# Connector.net
KiCad netlist of a schematic drawn in Altium Designer
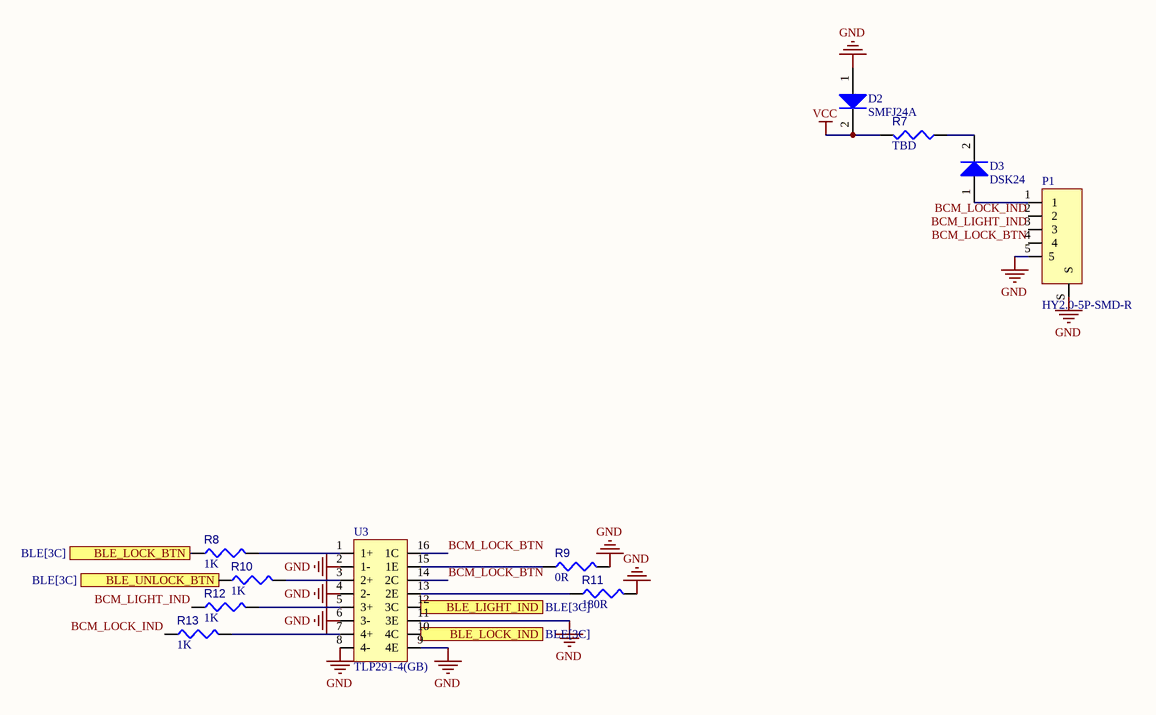
[diagram p0: Connector.SchDoc]

(export (version "E")
  (design (tool "Eeschema 10.0.6"))
  (components
    (comp (ref "D2")
      (value "SMFJ24A")
      (footprint "SOD-123FL")
      (description "TVS Diode")
      (libsource (lib "Database") (part "Diode Symbol"))
    )
    (comp (ref "D3")
      (value "DSK24")
      (footprint "SOD-123FL")
      (description "40V 2A Schottky barrier diode")
      (libsource (lib "Database") (part "Diode Symbol"))
    )
    (comp (ref "P1")
      (value "HY2.0-5P-SMD-R")
      (footprint "HY2.0-5P-SMD-R")
      (description "HY2.0 5P SMD Right angle")
      (libsource (lib "Database") (part "HY2.0-5P-SMD-R"))
    )
    (comp (ref "R7")
      (value "TBD")
      (footprint "RESC2013X70X40LL20T20")
      (description "0805 Universal Chip Resistor")
      (fields (field (name "Comment") "0805 Chip Resistor"))
      (libsource (lib "Database") (part "Chip Resistor"))
    )
    (comp (ref "R8")
      (value "1K")
      (footprint "RESC1608X55X25LL10T15")
      (description "0603 Chip Resistor")
      (fields (field (name "Comment") "1K 0603"))
      (libsource (lib "Database") (part "Chip Resistor"))
    )
    (comp (ref "R9")
      (value "0R")
      (footprint "RESC2013X70X40LL20T20")
      (description "0805 Chip Resistor")
      (fields (field (name "Comment") "0R 0805"))
      (libsource (lib "Database") (part "Chip Resistor"))
    )
    (comp (ref "R10")
      (value "1K")
      (footprint "RESC1608X55X25LL10T15")
      (description "0603 Chip Resistor")
      (fields (field (name "Comment") "1K 0603"))
      (libsource (lib "Database") (part "Chip Resistor"))
    )
    (comp (ref "R11")
      (value "180R")
      (footprint "RESC2013X70X40LL20T20")
      (description "0805 Chip Resistor")
      (fields (field (name "Comment") "180R 0805"))
      (libsource (lib "Database") (part "Chip Resistor"))
    )
    (comp (ref "R12")
      (value "1K")
      (footprint "RESC1608X55X25LL10T15")
      (description "0603 Chip Resistor")
      (fields (field (name "Comment") "1K 0603"))
      (libsource (lib "Database") (part "Chip Resistor"))
    )
    (comp (ref "R13")
      (value "1K")
      (footprint "RESC1608X55X25LL10T15")
      (description "0603 Chip Resistor")
      (fields (field (name "Comment") "1K 0603"))
      (libsource (lib "Database") (part "Chip Resistor"))
    )
    (comp (ref "U3")
      (value "TLP291-4(GB)")
      (footprint "SOP127P700X210-16L")
      (description "Photocouplers GaAs Infrared LED & Photo Transistor CTR 100")
      (libsource (lib "Database") (part "TLP291-4"))
    )
  )
  (nets
    (net (code "1") (name "/BCM_LIGHT_IND") (class "Default")
      (node (ref "P1") (pin "3") (pinfunction "3_3") (pintype "passive"))
      (node (ref "R12") (pin "1") (pinfunction "1_1") (pintype "passive"))
    )
    (net (code "2") (name "/BCM_LOCK_BTN") (class "Default")
      (node (ref "P1") (pin "4") (pinfunction "4_4") (pintype "passive"))
      (node (ref "U3") (pin "14") (pinfunction "2C_14") (pintype "passive"))
      (node (ref "U3") (pin "16") (pinfunction "1C_16") (pintype "passive"))
    )
    (net (code "3") (name "/BCM_LOCK_IND") (class "Default")
      (node (ref "P1") (pin "2") (pinfunction "2_2") (pintype "passive"))
      (node (ref "R13") (pin "1") (pinfunction "1_1") (pintype "passive"))
    )
    (net (code "4") (name "/BLE_LIGHT_IND") (class "Default")
      (node (ref "U3") (pin "12") (pinfunction "3C_12") (pintype "passive"))
    )
    (net (code "5") (name "/BLE_LOCK_BTN") (class "Default")
      (node (ref "R8") (pin "1") (pinfunction "1_1") (pintype "passive"))
    )
    (net (code "6") (name "/BLE_LOCK_IND") (class "Default")
      (node (ref "U3") (pin "10") (pinfunction "4C_10") (pintype "passive"))
    )
    (net (code "7") (name "/BLE_UNLOCK_BTN") (class "Default")
      (node (ref "R10") (pin "1") (pinfunction "1_1") (pintype "passive"))
    )
    (net (code "8") (name "GND") (class "Default")
      (node (ref "D2") (pin "1") (pinfunction "A_1") (pintype "passive"))
      (node (ref "P1") (pin "5") (pinfunction "5_5") (pintype "passive"))
      (node (ref "P1") (pin "S") (pinfunction "S_S") (pintype "passive"))
      (node (ref "R11") (pin "2") (pinfunction "2_2") (pintype "passive"))
      (node (ref "R9") (pin "2") (pinfunction "2_2") (pintype "passive"))
      (node (ref "U3") (pin "11") (pinfunction "3E_11") (pintype "passive"))
      (node (ref "U3") (pin "2") (pinfunction "1-_2") (pintype "passive"))
      (node (ref "U3") (pin "4") (pinfunction "2-_4") (pintype "passive"))
      (node (ref "U3") (pin "6") (pinfunction "3-_6") (pintype "passive"))
      (node (ref "U3") (pin "8") (pinfunction "4-_8") (pintype "passive"))
      (node (ref "U3") (pin "9") (pinfunction "4E_9") (pintype "passive"))
    )
    (net (code "9") (name "Net-(D3-A)") (class "Default")
      (node (ref "D3") (pin "1") (pinfunction "A_1") (pintype "passive"))
      (node (ref "P1") (pin "1") (pinfunction "1_1") (pintype "passive"))
    )
    (net (code "10") (name "Net-(D3-K)") (class "Default")
      (node (ref "D3") (pin "2") (pinfunction "K_2") (pintype "passive"))
      (node (ref "R7") (pin "1") (pinfunction "1_1") (pintype "passive"))
    )
    (net (code "11") (name "Net-(U3-1+)") (class "Default")
      (node (ref "R8") (pin "2") (pinfunction "2_2") (pintype "passive"))
      (node (ref "U3") (pin "1") (pinfunction "1+_1") (pintype "passive"))
    )
    (net (code "12") (name "Net-(U3-1E)") (class "Default")
      (node (ref "R9") (pin "1") (pinfunction "1_1") (pintype "passive"))
      (node (ref "U3") (pin "15") (pinfunction "1E_15") (pintype "passive"))
    )
    (net (code "13") (name "Net-(U3-2+)") (class "Default")
      (node (ref "R10") (pin "2") (pinfunction "2_2") (pintype "passive"))
      (node (ref "U3") (pin "3") (pinfunction "2+_3") (pintype "passive"))
    )
    (net (code "14") (name "Net-(U3-2E)") (class "Default")
      (node (ref "R11") (pin "1") (pinfunction "1_1") (pintype "passive"))
      (node (ref "U3") (pin "13") (pinfunction "2E_13") (pintype "passive"))
    )
    (net (code "15") (name "Net-(U3-3+)") (class "Default")
      (node (ref "R12") (pin "2") (pinfunction "2_2") (pintype "passive"))
      (node (ref "U3") (pin "5") (pinfunction "3+_5") (pintype "passive"))
    )
    (net (code "16") (name "Net-(U3-4+)") (class "Default")
      (node (ref "R13") (pin "2") (pinfunction "2_2") (pintype "passive"))
      (node (ref "U3") (pin "7") (pinfunction "4+_7") (pintype "passive"))
    )
    (net (code "17") (name "VCC") (class "Default")
      (node (ref "D2") (pin "2") (pinfunction "K_2") (pintype "passive"))
      (node (ref "R7") (pin "2") (pinfunction "2_2") (pintype "passive"))
    )
  )
)
